# Filter.net
KiCad netlist of a schematic drawn in Altium Designer
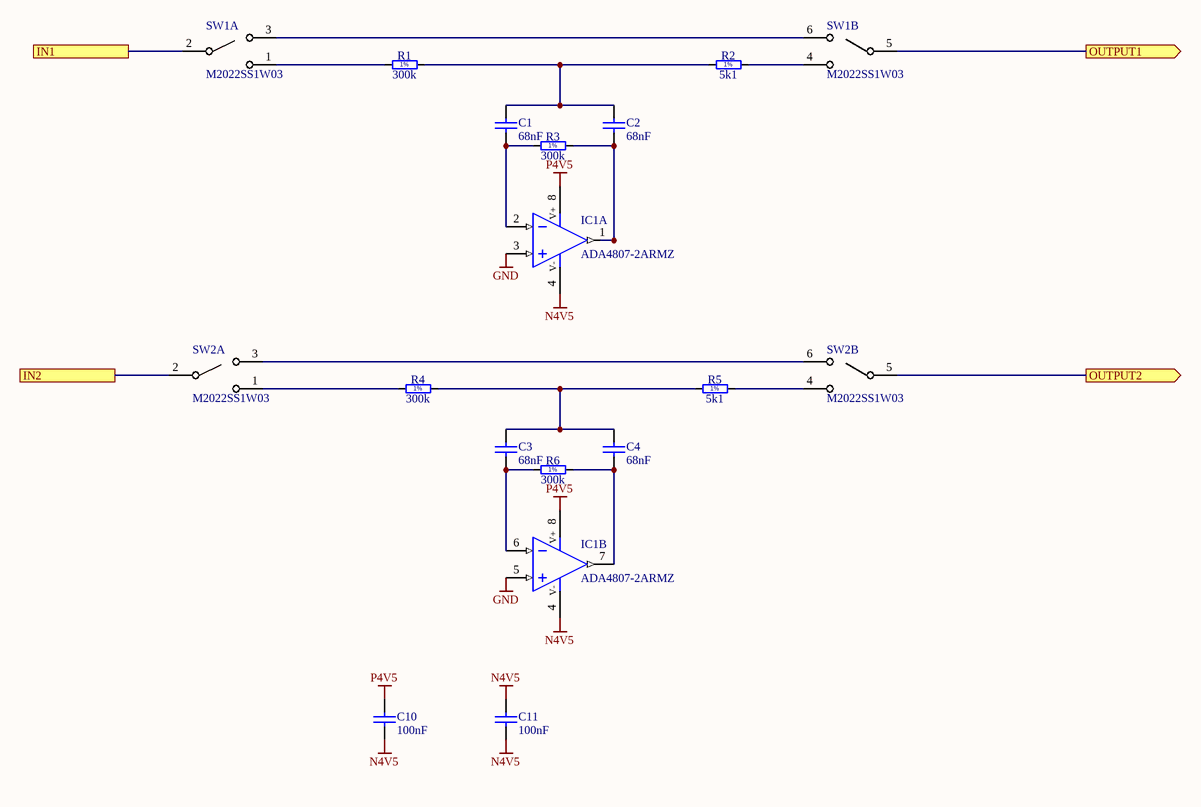
[diagram p0: Filter.SchDoc]

(export (version "E")
  (design (tool "Eeschema 10.0.6"))
  (components
    (comp (ref "C1")
      (value "68nF")
      (footprint "C0805C683KARACAUTO")
      (description "Cap Ceramic 0.068uF 250V X7R 10% Pad SMD 0805 125C Automotive T/R")
      (fields (field (name "TOLERANCE") "10%"))
      (libsource (lib "CapacitorLibrary") (part "C0805C683KARACAUTO"))
    )
    (comp (ref "C2")
      (value "68nF")
      (footprint "C0805C683KARACAUTO")
      (description "Cap Ceramic 0.068uF 250V X7R 10% Pad SMD 0805 125C Automotive T/R")
      (fields (field (name "TOLERANCE") "10%"))
      (libsource (lib "CapacitorLibrary") (part "C0805C683KARACAUTO"))
    )
    (comp (ref "C3")
      (value "68nF")
      (footprint "C0805C683KARACAUTO")
      (description "Cap Ceramic 0.068uF 250V X7R 10% Pad SMD 0805 125C Automotive T/R")
      (fields (field (name "TOLERANCE") "10%"))
      (libsource (lib "CapacitorLibrary") (part "C0805C683KARACAUTO"))
    )
    (comp (ref "C4")
      (value "68nF")
      (footprint "C0805C683KARACAUTO")
      (description "Cap Ceramic 0.068uF 250V X7R 10% Pad SMD 0805 125C Automotive T/R")
      (fields (field (name "TOLERANCE") "10%"))
      (libsource (lib "CapacitorLibrary") (part "C0805C683KARACAUTO"))
    )
    (comp (ref "C10")
      (value "100nF")
      (footprint "C0402C104K4RACTU")
      (description "Capacitor; Ceramic; Cap; .100uF; Tol 10%; SMT; Vol-Rtg 16V; X7R; Tape and Reel")
      (fields (field (name "TOLERANCE") "10%"))
      (libsource (lib "CapacitorLibrary") (part "C0402C104K4RACTU"))
    )
    (comp (ref "C11")
      (value "100nF")
      (footprint "C0402C104K4RACTU")
      (description "Capacitor; Ceramic; Cap; .100uF; Tol 10%; SMT; Vol-Rtg 16V; X7R; Tape and Reel")
      (fields (field (name "TOLERANCE") "10%"))
      (libsource (lib "CapacitorLibrary") (part "C0402C104K4RACTU"))
    )
    (comp (ref "IC1")
      (value "ADA4807-2ARMZ")
      (footprint "SOP65P490X110-8N")
      (description "Dual Operational Amplifier")
      (fields (field (name "MANUFACTURER") "ANALOG DEVICES") (field (name "AUTHOR") "CERN DEM MR"))
      (libsource (lib "ICs And Semiconductors") (part "Operational Amplifier x2 Type1"))
    )
    (comp (ref "R1")
      (value "300k")
      (footprint "RESC1608X55N")
      (description "Resistor - 1%")
      (fields
        (field (name "PART NUMBER") "R0603_300K_1%_0.1W_100PPM")
        (field (name "POWER") "0.1W")
        (field (name "AUTHOR") "CERN DEM JLC")
      )
      (libsource (lib "Resistors") (part "Resistor - 1%"))
    )
    (comp (ref "R2")
      (value "5k1")
      (footprint "RESC1608X55N")
      (description "Resistor - 1%")
      (fields
        (field (name "PART NUMBER") "R0603_5K1_1%_0.1W_100PPM")
        (field (name "POWER") "0.1W")
        (field (name "AUTHOR") "CERN DEM JLC")
      )
      (libsource (lib "Resistors") (part "Resistor - 1%"))
    )
    (comp (ref "R3")
      (value "300k")
      (footprint "RESC1608X55N")
      (description "Resistor - 1%")
      (fields
        (field (name "PART NUMBER") "R0603_300K_1%_0.1W_100PPM")
        (field (name "POWER") "0.1W")
        (field (name "AUTHOR") "CERN DEM JLC")
      )
      (libsource (lib "Resistors") (part "Resistor - 1%"))
    )
    (comp (ref "R4")
      (value "300k")
      (footprint "RESC1608X55N")
      (description "Resistor - 1%")
      (fields
        (field (name "PART NUMBER") "R0603_300K_1%_0.1W_100PPM")
        (field (name "POWER") "0.1W")
        (field (name "AUTHOR") "CERN DEM JLC")
      )
      (libsource (lib "Resistors") (part "Resistor - 1%"))
    )
    (comp (ref "R5")
      (value "5k1")
      (footprint "RESC1608X55N")
      (description "Resistor - 1%")
      (fields
        (field (name "PART NUMBER") "R0603_5K1_1%_0.1W_100PPM")
        (field (name "POWER") "0.1W")
        (field (name "AUTHOR") "CERN DEM JLC")
      )
      (libsource (lib "Resistors") (part "Resistor - 1%"))
    )
    (comp (ref "R6")
      (value "300k")
      (footprint "RESC1608X55N")
      (description "Resistor - 1%")
      (fields
        (field (name "PART NUMBER") "R0603_300K_1%_0.1W_100PPM")
        (field (name "POWER") "0.1W")
        (field (name "AUTHOR") "CERN DEM JLC")
      )
      (libsource (lib "Resistors") (part "Resistor - 1%"))
    )
    (comp (ref "SW1")
      (value "M2022SS1W03")
      (footprint "M2022SS1W03")
      (description "SWITCH TOGGLE DPDT 6A 125V ON-NONE-ON")
      (libsource (lib "InzLib") (part "M2022SS1W03"))
    )
    (comp (ref "SW2")
      (value "M2022SS1W03")
      (footprint "M2022SS1W03")
      (description "SWITCH TOGGLE DPDT 6A 125V ON-NONE-ON")
      (libsource (lib "") (part "M2022SS1W03_1"))
    )
  )
  (nets
    (net (code "1") (name "/IN1") (class "Default")
      (node (ref "SW1") (pin "2") (pinfunction "COM_2") (pintype "passive"))
    )
    (net (code "2") (name "/IN2") (class "Default")
      (node (ref "SW2") (pin "2") (pinfunction "COM_2") (pintype "passive"))
    )
    (net (code "3") (name "/OUTPUT1") (class "Default")
      (node (ref "SW1") (pin "5") (pinfunction "COM_5") (pintype "passive"))
    )
    (net (code "4") (name "/OUTPUT2") (class "Default")
      (node (ref "SW2") (pin "5") (pinfunction "COM_5") (pintype "passive"))
    )
    (net (code "5") (name "GND") (class "Default")
      (node (ref "IC1") (pin "3") (pinfunction "IN+_3") (pintype "input"))
      (node (ref "IC1") (pin "5") (pinfunction "IN+_5") (pintype "input"))
    )
    (net (code "6") (name "N4V5") (class "Default")
      (node (ref "C10") (pin "1") (pinfunction "1_1") (pintype "passive"))
      (node (ref "C11") (pin "1") (pinfunction "1_1") (pintype "passive"))
      (node (ref "C11") (pin "2") (pinfunction "2_2") (pintype "passive"))
      (node (ref "IC1") (pin "4") (pinfunction "V-_4") (pintype "power_in"))
    )
    (net (code "7") (name "Net-(C1-Pad2)") (class "Default")
      (node (ref "C1") (pin "2") (pinfunction "2_2") (pintype "passive"))
      (node (ref "C2") (pin "2") (pinfunction "2_2") (pintype "passive"))
      (node (ref "R1") (pin "2") (pinfunction "2_2") (pintype "passive"))
      (node (ref "R2") (pin "1") (pinfunction "1_1") (pintype "passive"))
    )
    (net (code "8") (name "Net-(C3-Pad2)") (class "Default")
      (node (ref "C3") (pin "2") (pinfunction "2_2") (pintype "passive"))
      (node (ref "C4") (pin "2") (pinfunction "2_2") (pintype "passive"))
      (node (ref "R4") (pin "2") (pinfunction "2_2") (pintype "passive"))
      (node (ref "R5") (pin "1") (pinfunction "1_1") (pintype "passive"))
    )
    (net (code "9") (name "Net-(IC1A-IN-)") (class "Default")
      (node (ref "C1") (pin "1") (pinfunction "1_1") (pintype "passive"))
      (node (ref "IC1") (pin "2") (pinfunction "IN-_2") (pintype "input"))
      (node (ref "R3") (pin "1") (pinfunction "1_1") (pintype "passive"))
    )
    (net (code "10") (name "Net-(IC1A-OUT)") (class "Default")
      (node (ref "C2") (pin "1") (pinfunction "1_1") (pintype "passive"))
      (node (ref "IC1") (pin "1") (pinfunction "OUT_1") (pintype "output"))
      (node (ref "R3") (pin "2") (pinfunction "2_2") (pintype "passive"))
    )
    (net (code "11") (name "Net-(IC1B-IN-)") (class "Default")
      (node (ref "C3") (pin "1") (pinfunction "1_1") (pintype "passive"))
      (node (ref "IC1") (pin "6") (pinfunction "IN-_6") (pintype "input"))
      (node (ref "R6") (pin "1") (pinfunction "1_1") (pintype "passive"))
    )
    (net (code "12") (name "Net-(IC1B-OUT)") (class "Default")
      (node (ref "C4") (pin "1") (pinfunction "1_1") (pintype "passive"))
      (node (ref "IC1") (pin "7") (pinfunction "OUT_7") (pintype "output"))
      (node (ref "R6") (pin "2") (pinfunction "2_2") (pintype "passive"))
    )
    (net (code "13") (name "Net-(SW1A-DOWN)") (class "Default")
      (node (ref "SW1") (pin "3") (pinfunction "DOWN_3") (pintype "passive"))
      (node (ref "SW1") (pin "6") (pinfunction "DOWN_6") (pintype "passive"))
    )
    (net (code "14") (name "Net-(SW1A-UP)") (class "Default")
      (node (ref "R1") (pin "1") (pinfunction "1_1") (pintype "passive"))
      (node (ref "SW1") (pin "1") (pinfunction "UP_1") (pintype "passive"))
    )
    (net (code "15") (name "Net-(SW1B-UP)") (class "Default")
      (node (ref "R2") (pin "2") (pinfunction "2_2") (pintype "passive"))
      (node (ref "SW1") (pin "4") (pinfunction "UP_4") (pintype "passive"))
    )
    (net (code "16") (name "Net-(SW2A-DOWN)") (class "Default")
      (node (ref "SW2") (pin "3") (pinfunction "DOWN_3") (pintype "passive"))
      (node (ref "SW2") (pin "6") (pinfunction "DOWN_6") (pintype "passive"))
    )
    (net (code "17") (name "Net-(SW2A-UP)") (class "Default")
      (node (ref "R4") (pin "1") (pinfunction "1_1") (pintype "passive"))
      (node (ref "SW2") (pin "1") (pinfunction "UP_1") (pintype "passive"))
    )
    (net (code "18") (name "Net-(SW2B-UP)") (class "Default")
      (node (ref "R5") (pin "2") (pinfunction "2_2") (pintype "passive"))
      (node (ref "SW2") (pin "4") (pinfunction "UP_4") (pintype "passive"))
    )
    (net (code "19") (name "P4V5") (class "Default")
      (node (ref "C10") (pin "2") (pinfunction "2_2") (pintype "passive"))
      (node (ref "IC1") (pin "8") (pinfunction "V+_8") (pintype "power_in"))
    )
  )
)
